# gimli1.net
KiCad netlist of a schematic drawn in EAGLE
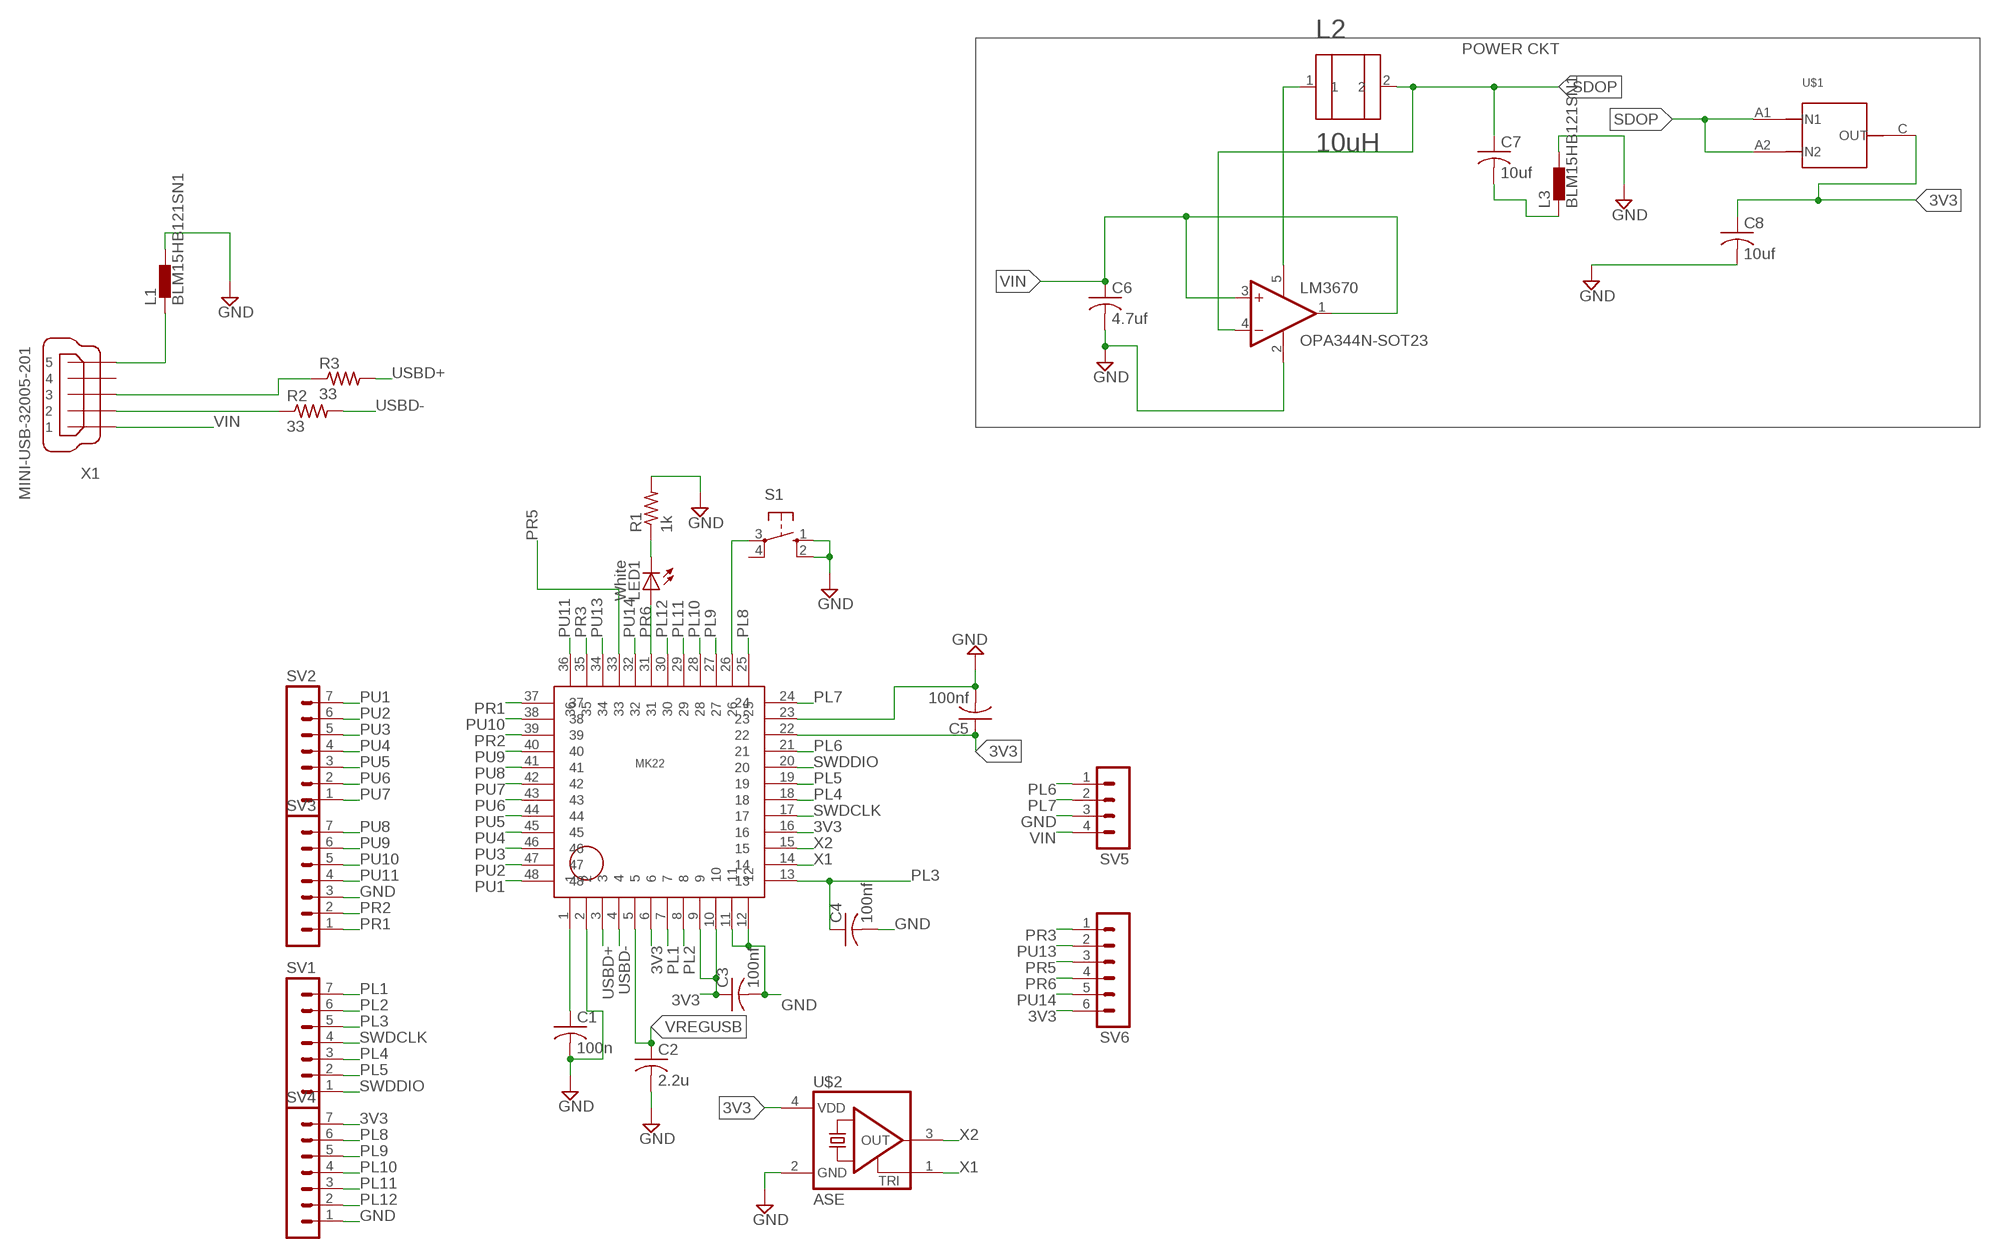
[diagram p0: schematic, sheet 1]

(export (version "E")
  (design (tool "Eeschema 10.0.6"))
  (components
    (comp (ref "C1")
      (value "100n")
      (footprint "eagle-import:C0402")
      (libsource (lib "eagle-import") (part "C-USC0402"))
    )
    (comp (ref "C2")
      (value "2.2u")
      (footprint "eagle-import:C0402")
      (libsource (lib "eagle-import") (part "C-USC0402"))
    )
    (comp (ref "C3")
      (value "100nf")
      (footprint "eagle-import:C0402")
      (libsource (lib "eagle-import") (part "C-USC0402"))
    )
    (comp (ref "C4")
      (value "100nf")
      (footprint "eagle-import:C0402")
      (libsource (lib "eagle-import") (part "C-USC0402"))
    )
    (comp (ref "C5")
      (value "100nf")
      (footprint "eagle-import:C0402")
      (libsource (lib "eagle-import") (part "C-USC0402"))
    )
    (comp (ref "C6")
      (value "4.7uf")
      (footprint "eagle-import:C0402")
      (libsource (lib "eagle-import") (part "C-USC0402"))
    )
    (comp (ref "C7")
      (value "10uf")
      (footprint "eagle-import:C0402")
      (libsource (lib "eagle-import") (part "C-USC0402"))
    )
    (comp (ref "C8")
      (value "10uf")
      (footprint "eagle-import:C0402")
      (libsource (lib "eagle-import") (part "C-USC0402"))
    )
    (comp (ref "L1")
      (value "BLM15HB121SN1")
      (footprint "eagle-import:0402")
      (libsource (lib "eagle-import") (part "BLM15HB121SN1"))
    )
    (comp (ref "L2")
      (value "10uH")
      (footprint "eagle-import:INDUCTNEW")
      (libsource (lib "eagle-import") (part "INDUCTNEW"))
    )
    (comp (ref "L3")
      (value "BLM15HB121SN1")
      (footprint "eagle-import:0402")
      (libsource (lib "eagle-import") (part "BLM15HB121SN1"))
    )
    (comp (ref "LED1")
      (value "White")
      (footprint "eagle-import:SML0603")
      (libsource (lib "eagle-import") (part "LEDSML0603"))
    )
    (comp (ref "LM3670")
      (value "OPA344N-SOT23")
      (footprint "eagle-import:SOT23-5")
      (libsource (lib "eagle-import") (part "OPA-SOT23344N"))
    )
    (comp (ref "MK22")
      (value "LQFP48")
      (footprint "eagle-import:LQFP48")
      (libsource (lib "eagle-import") (part "LQFP48"))
    )
    (comp (ref "R1")
      (value "1k")
      (footprint "eagle-import:R0402")
      (libsource (lib "eagle-import") (part "R-US_R0402"))
    )
    (comp (ref "R2")
      (value "33")
      (footprint "eagle-import:R0402")
      (libsource (lib "eagle-import") (part "R-US_R0402"))
    )
    (comp (ref "R3")
      (value "33")
      (footprint "eagle-import:R0402")
      (libsource (lib "eagle-import") (part "R-US_R0402"))
    )
    (comp (ref "S1")
      (value "10-XX")
      (footprint "eagle-import:B3F-10XX")
      (fields (field (name "MPN") "B3F-1000"))
      (libsource (lib "eagle-import") (part "10-XX"))
    )
    (comp (ref "SV1")
      (value "MA07-1")
      (footprint "eagle-import:MA07-1")
      (libsource (lib "eagle-import") (part "MA07-1"))
    )
    (comp (ref "SV2")
      (value "MA07-1")
      (footprint "eagle-import:MA07-1")
      (libsource (lib "eagle-import") (part "MA07-1"))
    )
    (comp (ref "SV3")
      (value "MA07-1")
      (footprint "eagle-import:MA07-1")
      (libsource (lib "eagle-import") (part "MA07-1"))
    )
    (comp (ref "SV4")
      (value "MA07-1")
      (footprint "eagle-import:MA07-1")
      (libsource (lib "eagle-import") (part "MA07-1"))
    )
    (comp (ref "SV5")
      (value "MA04-1")
      (footprint "eagle-import:MA04-1")
      (libsource (lib "eagle-import") (part "MA04-1"))
    )
    (comp (ref "SV6")
      (value "MA06-1")
      (footprint "eagle-import:MA06-1")
      (libsource (lib "eagle-import") (part "MA06-1"))
    )
    (comp (ref "U$1")
      (value "DIODEDPAK")
      (footprint "eagle-import:DPACK_3")
      (libsource (lib "eagle-import") (part "DIODEDPAK"))
    )
    (comp (ref "U$2")
      (value "ASE")
      (footprint "eagle-import:ASE")
      (libsource (lib "eagle-import") (part "ASE"))
    )
    (comp (ref "X1")
      (value "MINI-USB-32005-201")
      (footprint "eagle-import:32005-201")
      (libsource (lib "eagle-import") (part "MINI-USB-32005-201"))
    )
  )
  (nets
    (net (code "1") (name "/PL1") (class "Default")
      (node (ref "MK22") (pin "7") (pinfunction "7_7") (pintype "bidirectional"))
      (node (ref "SV1") (pin "7") (pinfunction "7_7") (pintype "passive"))
    )
    (net (code "2") (name "/PL2") (class "Default")
      (node (ref "MK22") (pin "8") (pinfunction "8_8") (pintype "bidirectional"))
      (node (ref "SV1") (pin "6") (pinfunction "6_6") (pintype "passive"))
    )
    (net (code "3") (name "/PL3") (class "Default")
      (node (ref "C4") (pin "1") (pinfunction "1_1") (pintype "passive"))
      (node (ref "MK22") (pin "13") (pinfunction "13_13") (pintype "bidirectional"))
      (node (ref "SV1") (pin "5") (pinfunction "5_5") (pintype "passive"))
    )
    (net (code "4") (name "/PL4") (class "Default")
      (node (ref "MK22") (pin "18") (pinfunction "18_18") (pintype "bidirectional"))
      (node (ref "SV1") (pin "3") (pinfunction "3_3") (pintype "passive"))
    )
    (net (code "5") (name "/PL5") (class "Default")
      (node (ref "MK22") (pin "19") (pinfunction "19_19") (pintype "bidirectional"))
      (node (ref "SV1") (pin "2") (pinfunction "2_2") (pintype "passive"))
    )
    (net (code "6") (name "/PL6") (class "Default")
      (node (ref "MK22") (pin "21") (pinfunction "21_21") (pintype "bidirectional"))
      (node (ref "SV5") (pin "1") (pinfunction "1_1") (pintype "passive"))
    )
    (net (code "7") (name "/PL7") (class "Default")
      (node (ref "MK22") (pin "24") (pinfunction "24_24") (pintype "bidirectional"))
      (node (ref "SV5") (pin "2") (pinfunction "2_2") (pintype "passive"))
    )
    (net (code "8") (name "/PL8") (class "Default")
      (node (ref "MK22") (pin "25") (pinfunction "25_25") (pintype "bidirectional"))
      (node (ref "SV4") (pin "6") (pinfunction "6_6") (pintype "passive"))
    )
    (net (code "9") (name "/PL9") (class "Default")
      (node (ref "MK22") (pin "27") (pinfunction "27_27") (pintype "bidirectional"))
      (node (ref "SV4") (pin "5") (pinfunction "5_5") (pintype "passive"))
    )
    (net (code "10") (name "/PL10") (class "Default")
      (node (ref "MK22") (pin "28") (pinfunction "28_28") (pintype "bidirectional"))
      (node (ref "SV4") (pin "4") (pinfunction "4_4") (pintype "passive"))
    )
    (net (code "11") (name "/PL11") (class "Default")
      (node (ref "MK22") (pin "29") (pinfunction "29_29") (pintype "bidirectional"))
      (node (ref "SV4") (pin "3") (pinfunction "3_3") (pintype "passive"))
    )
    (net (code "12") (name "/PL12") (class "Default")
      (node (ref "MK22") (pin "30") (pinfunction "30_30") (pintype "bidirectional"))
      (node (ref "SV4") (pin "2") (pinfunction "2_2") (pintype "passive"))
    )
    (net (code "13") (name "/PR1") (class "Default")
      (node (ref "MK22") (pin "37") (pinfunction "37_37") (pintype "bidirectional"))
      (node (ref "SV3") (pin "1") (pinfunction "1_1") (pintype "passive"))
    )
    (net (code "14") (name "/PR2") (class "Default")
      (node (ref "MK22") (pin "39") (pinfunction "39_39") (pintype "bidirectional"))
      (node (ref "SV3") (pin "2") (pinfunction "2_2") (pintype "passive"))
    )
    (net (code "15") (name "/PR3") (class "Default")
      (node (ref "MK22") (pin "35") (pinfunction "35_35") (pintype "bidirectional"))
      (node (ref "SV6") (pin "1") (pinfunction "1_1") (pintype "passive"))
    )
    (net (code "16") (name "/PR5") (class "Default")
      (node (ref "MK22") (pin "33") (pinfunction "33_33") (pintype "bidirectional"))
      (node (ref "SV6") (pin "3") (pinfunction "3_3") (pintype "passive"))
    )
    (net (code "17") (name "/PR6") (class "Default")
      (node (ref "LED1") (pin "A") (pinfunction "A_A") (pintype "passive"))
      (node (ref "MK22") (pin "31") (pinfunction "31_31") (pintype "bidirectional"))
      (node (ref "SV6") (pin "4") (pinfunction "4_4") (pintype "passive"))
    )
    (net (code "18") (name "/PU1") (class "Default")
      (node (ref "MK22") (pin "48") (pinfunction "48_48") (pintype "bidirectional"))
      (node (ref "SV2") (pin "7") (pinfunction "7_7") (pintype "passive"))
    )
    (net (code "19") (name "/PU2") (class "Default")
      (node (ref "MK22") (pin "47") (pinfunction "47_47") (pintype "bidirectional"))
      (node (ref "SV2") (pin "6") (pinfunction "6_6") (pintype "passive"))
    )
    (net (code "20") (name "/PU3") (class "Default")
      (node (ref "MK22") (pin "46") (pinfunction "46_46") (pintype "bidirectional"))
      (node (ref "SV2") (pin "5") (pinfunction "5_5") (pintype "passive"))
    )
    (net (code "21") (name "/PU4") (class "Default")
      (node (ref "MK22") (pin "45") (pinfunction "45_45") (pintype "bidirectional"))
      (node (ref "SV2") (pin "4") (pinfunction "4_4") (pintype "passive"))
    )
    (net (code "22") (name "/PU5") (class "Default")
      (node (ref "MK22") (pin "44") (pinfunction "44_44") (pintype "bidirectional"))
      (node (ref "SV2") (pin "3") (pinfunction "3_3") (pintype "passive"))
    )
    (net (code "23") (name "/PU6") (class "Default")
      (node (ref "MK22") (pin "43") (pinfunction "43_43") (pintype "bidirectional"))
      (node (ref "SV2") (pin "2") (pinfunction "2_2") (pintype "passive"))
    )
    (net (code "24") (name "/PU7") (class "Default")
      (node (ref "MK22") (pin "42") (pinfunction "42_42") (pintype "bidirectional"))
      (node (ref "SV2") (pin "1") (pinfunction "1_1") (pintype "passive"))
    )
    (net (code "25") (name "/PU8") (class "Default")
      (node (ref "MK22") (pin "41") (pinfunction "41_41") (pintype "bidirectional"))
      (node (ref "SV3") (pin "7") (pinfunction "7_7") (pintype "passive"))
    )
    (net (code "26") (name "/PU9") (class "Default")
      (node (ref "MK22") (pin "40") (pinfunction "40_40") (pintype "bidirectional"))
      (node (ref "SV3") (pin "6") (pinfunction "6_6") (pintype "passive"))
    )
    (net (code "27") (name "/PU10") (class "Default")
      (node (ref "MK22") (pin "38") (pinfunction "38_38") (pintype "bidirectional"))
      (node (ref "SV3") (pin "5") (pinfunction "5_5") (pintype "passive"))
    )
    (net (code "28") (name "/PU11") (class "Default")
      (node (ref "MK22") (pin "36") (pinfunction "36_36") (pintype "bidirectional"))
      (node (ref "SV3") (pin "4") (pinfunction "4_4") (pintype "passive"))
    )
    (net (code "29") (name "/PU13") (class "Default")
      (node (ref "MK22") (pin "34") (pinfunction "34_34") (pintype "bidirectional"))
      (node (ref "SV6") (pin "2") (pinfunction "2_2") (pintype "passive"))
    )
    (net (code "30") (name "/PU14") (class "Default")
      (node (ref "MK22") (pin "32") (pinfunction "32_32") (pintype "bidirectional"))
      (node (ref "SV6") (pin "5") (pinfunction "5_5") (pintype "passive"))
    )
    (net (code "31") (name "/SWDCLK") (class "Default")
      (node (ref "MK22") (pin "17") (pinfunction "17_17") (pintype "bidirectional"))
      (node (ref "SV1") (pin "4") (pinfunction "4_4") (pintype "passive"))
    )
    (net (code "32") (name "/SWDDIO") (class "Default")
      (node (ref "MK22") (pin "20") (pinfunction "20_20") (pintype "bidirectional"))
      (node (ref "SV1") (pin "1") (pinfunction "1_1") (pintype "passive"))
    )
    (net (code "33") (name "/USBD+") (class "Default")
      (node (ref "MK22") (pin "3") (pinfunction "3_3") (pintype "bidirectional"))
      (node (ref "R3") (pin "2") (pinfunction "2_2") (pintype "passive"))
    )
    (net (code "34") (name "/USBD-") (class "Default")
      (node (ref "MK22") (pin "4") (pinfunction "4_4") (pintype "bidirectional"))
      (node (ref "R2") (pin "2") (pinfunction "2_2") (pintype "passive"))
    )
    (net (code "35") (name "/X1") (class "Default")
      (node (ref "MK22") (pin "14") (pinfunction "14_14") (pintype "bidirectional"))
      (node (ref "U$2") (pin "1") (pinfunction "TRI_1") (pintype "input"))
    )
    (net (code "36") (name "/X2") (class "Default")
      (node (ref "MK22") (pin "15") (pinfunction "15_15") (pintype "bidirectional"))
      (node (ref "U$2") (pin "3") (pinfunction "OUT_3") (pintype "output"))
    )
    (net (code "37") (name "3V3") (class "Default")
      (node (ref "C3") (pin "1") (pinfunction "1_1") (pintype "passive"))
      (node (ref "C5") (pin "1") (pinfunction "1_1") (pintype "passive"))
      (node (ref "C8") (pin "1") (pinfunction "1_1") (pintype "passive"))
      (node (ref "MK22") (pin "10") (pinfunction "10_10") (pintype "bidirectional"))
      (node (ref "MK22") (pin "16") (pinfunction "16_16") (pintype "bidirectional"))
      (node (ref "MK22") (pin "22") (pinfunction "22_22") (pintype "bidirectional"))
      (node (ref "MK22") (pin "6") (pinfunction "6_6") (pintype "bidirectional"))
      (node (ref "MK22") (pin "9") (pinfunction "9_9") (pintype "bidirectional"))
      (node (ref "SV4") (pin "7") (pinfunction "7_7") (pintype "passive"))
      (node (ref "SV6") (pin "6") (pinfunction "6_6") (pintype "passive"))
      (node (ref "U$1") (pin "C") (pinfunction "OUT_C") (pintype "bidirectional"))
      (node (ref "U$2") (pin "4") (pinfunction "VDD_4") (pintype "power_in"))
    )
    (net (code "38") (name "GND") (class "Default")
      (node (ref "C1") (pin "2") (pinfunction "2_2") (pintype "passive"))
      (node (ref "C2") (pin "2") (pinfunction "2_2") (pintype "passive"))
      (node (ref "C3") (pin "2") (pinfunction "2_2") (pintype "passive"))
      (node (ref "C4") (pin "2") (pinfunction "2_2") (pintype "passive"))
      (node (ref "C5") (pin "2") (pinfunction "2_2") (pintype "passive"))
      (node (ref "C6") (pin "2") (pinfunction "2_2") (pintype "passive"))
      (node (ref "C8") (pin "2") (pinfunction "2_2") (pintype "passive"))
      (node (ref "L1") (pin "1") (pinfunction "1_1") (pintype "passive"))
      (node (ref "L1") (pin "2") (pinfunction "2_2") (pintype "passive"))
      (node (ref "L3") (pin "2") (pinfunction "2_2") (pintype "passive"))
      (node (ref "LM3670") (pin "2") (pinfunction "V-_2") (pintype "power_in"))
      (node (ref "MK22") (pin "11") (pinfunction "11_11") (pintype "bidirectional"))
      (node (ref "MK22") (pin "12") (pinfunction "12_12") (pintype "bidirectional"))
      (node (ref "MK22") (pin "2") (pinfunction "2_2") (pintype "bidirectional"))
      (node (ref "MK22") (pin "23") (pinfunction "23_23") (pintype "bidirectional"))
      (node (ref "R1") (pin "2") (pinfunction "2_2") (pintype "passive"))
      (node (ref "S1") (pin "1") (pinfunction "S_1") (pintype "passive"))
      (node (ref "S1") (pin "2") (pinfunction "S1_2") (pintype "passive"))
      (node (ref "SV3") (pin "3") (pinfunction "3_3") (pintype "passive"))
      (node (ref "SV4") (pin "1") (pinfunction "1_1") (pintype "passive"))
      (node (ref "SV5") (pin "3") (pinfunction "3_3") (pintype "passive"))
      (node (ref "U$2") (pin "2") (pinfunction "GND_2") (pintype "power_in"))
      (node (ref "X1") (pin "5") (pinfunction "5_5") (pintype "passive"))
    )
    (net (code "39") (name "Net-(C1-Pad1)") (class "Default")
      (node (ref "C1") (pin "1") (pinfunction "1_1") (pintype "passive"))
      (node (ref "MK22") (pin "1") (pinfunction "1_1") (pintype "bidirectional"))
    )
    (net (code "40") (name "Net-(C7-Pad2)") (class "Default")
      (node (ref "C7") (pin "2") (pinfunction "2_2") (pintype "passive"))
      (node (ref "L3") (pin "1") (pinfunction "1_1") (pintype "passive"))
    )
    (net (code "41") (name "Net-(LED1-PadC)") (class "Default")
      (node (ref "LED1") (pin "C") (pinfunction "C_C") (pintype "passive"))
      (node (ref "R1") (pin "1") (pinfunction "1_1") (pintype "passive"))
    )
    (net (code "42") (name "Net-(LM3670-V+)") (class "Default")
      (node (ref "L2") (pin "1") (pinfunction "1_1") (pintype "bidirectional"))
      (node (ref "LM3670") (pin "5") (pinfunction "V+_5") (pintype "power_in"))
    )
    (net (code "43") (name "Net-(R2-Pad1)") (class "Default")
      (node (ref "R2") (pin "1") (pinfunction "1_1") (pintype "passive"))
      (node (ref "X1") (pin "2") (pinfunction "2_2") (pintype "passive"))
    )
    (net (code "44") (name "Net-(R3-Pad1)") (class "Default")
      (node (ref "R3") (pin "1") (pinfunction "1_1") (pintype "passive"))
      (node (ref "X1") (pin "3") (pinfunction "3_3") (pintype "passive"))
    )
    (net (code "45") (name "Net-(S1-P)") (class "Default")
      (node (ref "MK22") (pin "26") (pinfunction "26_26") (pintype "bidirectional"))
      (node (ref "S1") (pin "3") (pinfunction "P_3") (pintype "passive"))
    )
    (net (code "46") (name "SDOP") (class "Default")
      (node (ref "C7") (pin "1") (pinfunction "1_1") (pintype "passive"))
      (node (ref "L2") (pin "2") (pinfunction "2_2") (pintype "bidirectional"))
      (node (ref "LM3670") (pin "4") (pinfunction "-IN_4") (pintype "input"))
      (node (ref "U$1") (pin "A1") (pinfunction "IN1_A1") (pintype "bidirectional"))
      (node (ref "U$1") (pin "A2") (pinfunction "IN2_A2") (pintype "bidirectional"))
    )
    (net (code "47") (name "VIN") (class "Default")
      (node (ref "C6") (pin "1") (pinfunction "1_1") (pintype "passive"))
      (node (ref "LM3670") (pin "1") (pinfunction "OUT_1") (pintype "output"))
      (node (ref "LM3670") (pin "3") (pinfunction "+IN_3") (pintype "input"))
      (node (ref "SV5") (pin "4") (pinfunction "4_4") (pintype "passive"))
      (node (ref "X1") (pin "1") (pinfunction "1_1") (pintype "passive"))
    )
    (net (code "48") (name "VREGUSB") (class "Default")
      (node (ref "C2") (pin "1") (pinfunction "1_1") (pintype "passive"))
      (node (ref "MK22") (pin "5") (pinfunction "5_5") (pintype "bidirectional"))
    )
    (net (code "49") (name "unconnected-(S1-P1-Pad4)") (class "Default")
      (node (ref "S1") (pin "4") (pinfunction "P1_4") (pintype "passive"))
    )
    (net (code "50") (name "unconnected-(X1-Pad4)") (class "Default")
      (node (ref "X1") (pin "4") (pinfunction "4_4") (pintype "passive"))
    )
  )
)
